# schematic-cnc.net
KiCad netlist of a schematic drawn in EAGLE
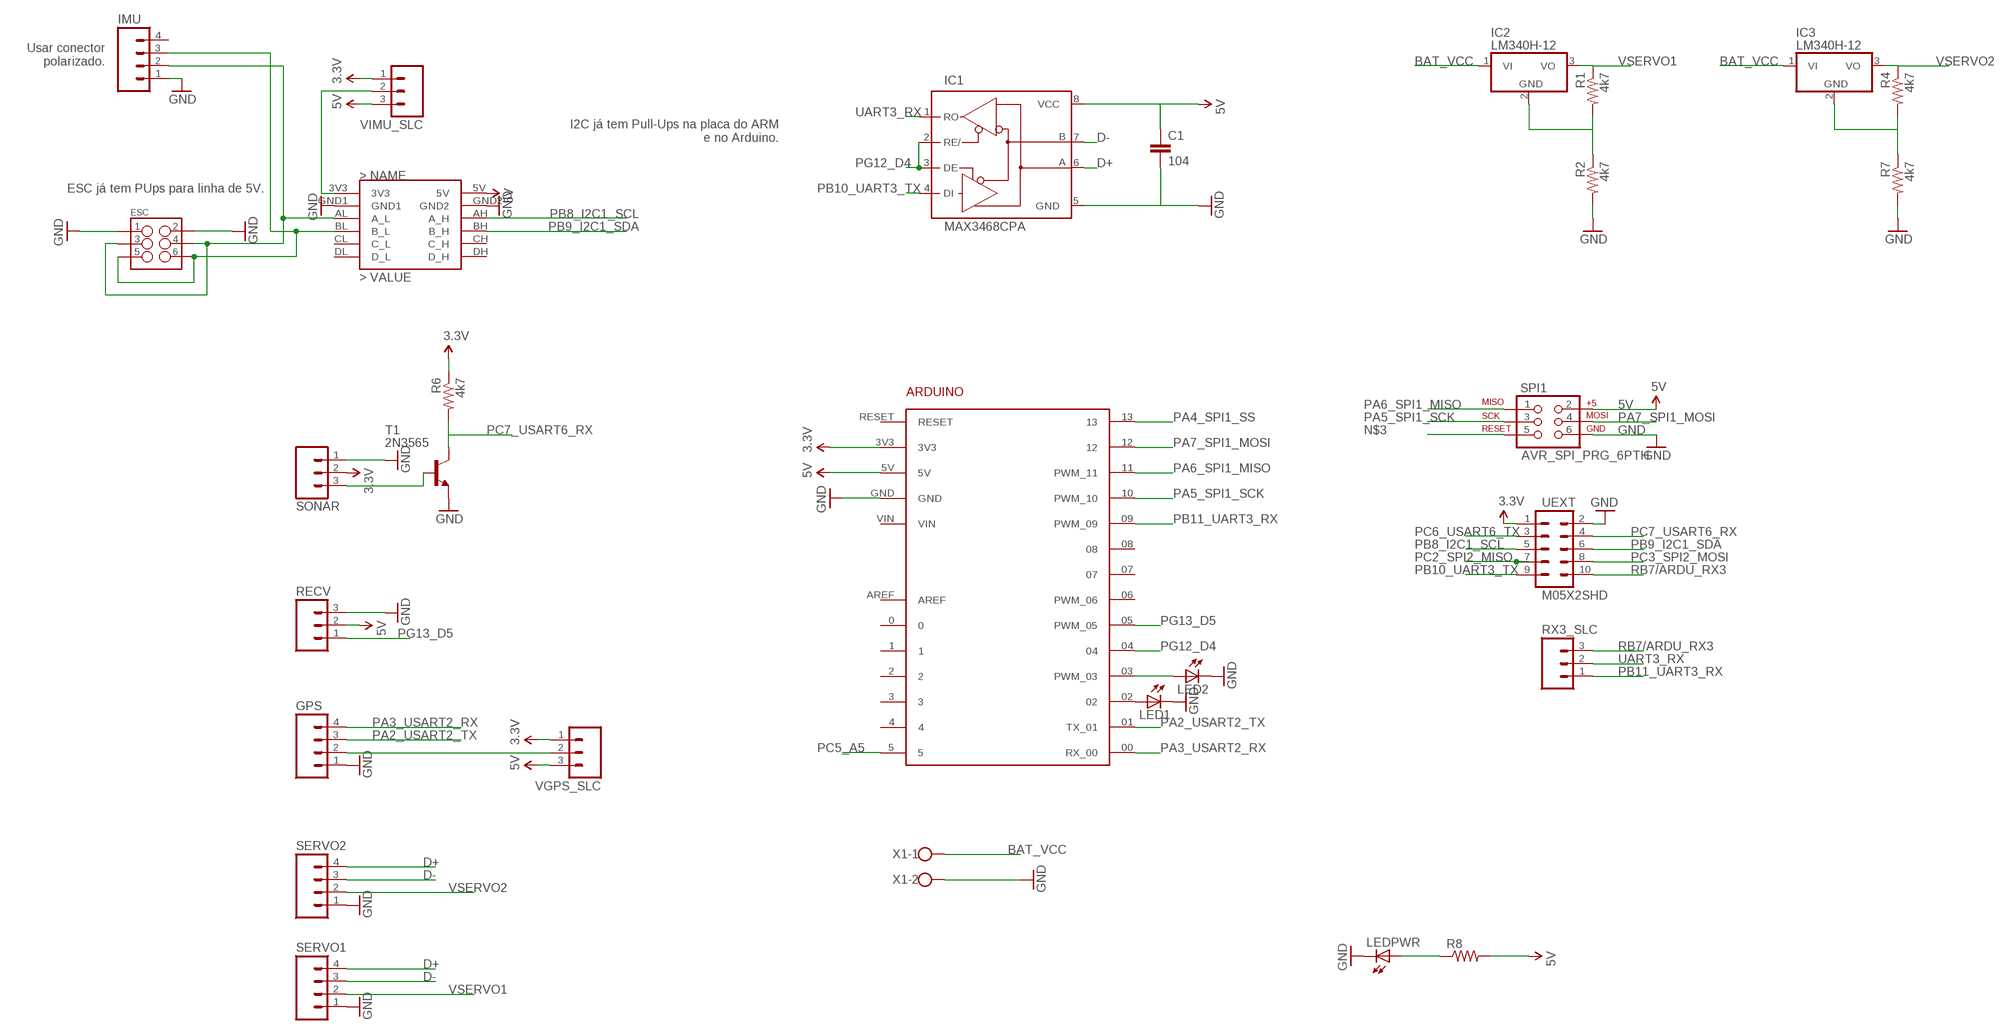
[diagram p0: schematic, sheet 1]

(export (version "E")
  (design (tool "Eeschema 10.0.6"))
  (components
    (comp (ref "ARDUINO1")
      (value "ARDUINO")
      (footprint "eagle-import:ARDUINO")
      (libsource (lib "eagle-import") (part "ARDUINO"))
    )
    (comp (ref "C1")
      (value "104")
      (footprint "eagle-import:CAP-PTH-SMALL-KIT")
      (libsource (lib "eagle-import") (part "0.1UF-50V-20%(PTH)KIT-EZ"))
    )
    (comp (ref "ESC")
      (value "M03X22X3_SILK_SM")
      (footprint "eagle-import:2X3")
      (libsource (lib "eagle-import") (part "M03X22X3_SILK_SM"))
    )
    (comp (ref "GPS")
      (value "M04PTH")
      (footprint "eagle-import:1X04")
      (libsource (lib "eagle-import") (part "M04PTH"))
    )
    (comp (ref "IC1")
      (value "MAX3468CPA")
      (footprint "eagle-import:DIL08")
      (libsource (lib "eagle-import") (part "MAX34PA68C"))
    )
    (comp (ref "IC2")
      (value "LM340H-12")
      (footprint "eagle-import:TO220H")
      (libsource (lib "eagle-import") (part "LM340?-H12"))
    )
    (comp (ref "IC3")
      (value "LM340H-12")
      (footprint "eagle-import:TO220H")
      (libsource (lib "eagle-import") (part "LM340?-H12"))
    )
    (comp (ref "IMU")
      (value "M04PTH")
      (footprint "eagle-import:1X04")
      (libsource (lib "eagle-import") (part "M04PTH"))
    )
    (comp (ref "LED1")
      (value "LED3MM")
      (footprint "eagle-import:LED3MM")
      (libsource (lib "eagle-import") (part "LED3MM"))
    )
    (comp (ref "LED2")
      (value "LED3MM")
      (footprint "eagle-import:LED3MM")
      (libsource (lib "eagle-import") (part "LED3MM"))
    )
    (comp (ref "LEDPWR")
      (value "LED3MM")
      (footprint "eagle-import:LED3MM")
      (libsource (lib "eagle-import") (part "LED3MM"))
    )
    (comp (ref "R1")
      (value "4k7")
      (footprint "eagle-import:0309V")
      (libsource (lib "eagle-import") (part "R-US_0309/V"))
    )
    (comp (ref "R2")
      (value "4k7")
      (footprint "eagle-import:0204_7")
      (libsource (lib "eagle-import") (part "R-US_0204/7"))
    )
    (comp (ref "R4")
      (value "4k7")
      (footprint "eagle-import:0309V")
      (libsource (lib "eagle-import") (part "R-US_0309/V"))
    )
    (comp (ref "R6")
      (value "4k7")
      (footprint "eagle-import:0204_7")
      (libsource (lib "eagle-import") (part "R-US_0204/7"))
    )
    (comp (ref "R7")
      (value "4k7")
      (footprint "eagle-import:0204_7")
      (libsource (lib "eagle-import") (part "R-US_0204/7"))
    )
    (comp (ref "R8")
      (value "RESISTORPTH-1/6W")
      (footprint "eagle-import:1_6W-RES")
      (libsource (lib "eagle-import") (part "RESISTORPTH-1/6W"))
    )
    (comp (ref "RECV")
      (value "M03PTH")
      (footprint "eagle-import:1X03")
      (libsource (lib "eagle-import") (part "M03PTH"))
    )
    (comp (ref "RX3_SLC")
      (value "M03PTH")
      (footprint "eagle-import:1X03")
      (libsource (lib "eagle-import") (part "M03PTH"))
    )
    (comp (ref "SERVO1")
      (value "M04PTH")
      (footprint "eagle-import:1X04")
      (libsource (lib "eagle-import") (part "M04PTH"))
    )
    (comp (ref "SERVO2")
      (value "M04PTH")
      (footprint "eagle-import:1X04")
      (libsource (lib "eagle-import") (part "M04PTH"))
    )
    (comp (ref "SONAR")
      (value "M03PTH")
      (footprint "eagle-import:1X03")
      (libsource (lib "eagle-import") (part "M03PTH"))
    )
    (comp (ref "SPI1")
      (value "AVR_SPI_PRG_6PTH")
      (footprint "eagle-import:2X3")
      (libsource (lib "eagle-import") (part "AVR_SPI_PRG_6PTH"))
    )
    (comp (ref "T1")
      (value "2N3565")
      (footprint "eagle-import:TO92")
      (libsource (lib "eagle-import") (part "2N3565"))
    )
    (comp (ref "U$1")
      (value "JYMCU_LOGIC_LEVEL_CONVERTER")
      (footprint "eagle-import:JYMCU_LOGIC_LEVEL_SHIFTER_DIP")
      (libsource (lib "eagle-import") (part "JYMCU_LOGIC_LEVEL_CONVERTER"))
    )
    (comp (ref "UEXT")
      (value "M05X2SHD")
      (footprint "eagle-import:2X5-SHROUDED")
      (libsource (lib "eagle-import") (part "M05X2SHD"))
    )
    (comp (ref "VGPS_SLC")
      (value "M03PTH")
      (footprint "eagle-import:1X03")
      (libsource (lib "eagle-import") (part "M03PTH"))
    )
    (comp (ref "VIMU_SLC")
      (value "M03PTH")
      (footprint "eagle-import:1X03")
      (libsource (lib "eagle-import") (part "M03PTH"))
    )
    (comp (ref "X1")
      (value "W237-102")
      (footprint "eagle-import:W237-102")
      (fields (field (name "MPN") "237-102"))
      (libsource (lib "eagle-import") (part "W237-102"))
    )
  )
  (nets
    (net (code "1") (name "/BAT_VCC") (class "Default")
      (node (ref "IC2") (pin "1") (pinfunction "VI_1") (pintype "input"))
      (node (ref "IC3") (pin "1") (pinfunction "VI_1") (pintype "input"))
      (node (ref "X1") (pin "1") (pinfunction "KL_1") (pintype "passive"))
    )
    (net (code "2") (name "/D+") (class "Default")
      (node (ref "IC1") (pin "6") (pinfunction "A_6") (pintype "passive"))
      (node (ref "SERVO1") (pin "4") (pinfunction "4_4") (pintype "passive"))
      (node (ref "SERVO2") (pin "4") (pinfunction "4_4") (pintype "passive"))
    )
    (net (code "3") (name "/D-") (class "Default")
      (node (ref "IC1") (pin "7") (pinfunction "B_7") (pintype "passive"))
      (node (ref "SERVO1") (pin "3") (pinfunction "3_3") (pintype "passive"))
      (node (ref "SERVO2") (pin "3") (pinfunction "3_3") (pintype "passive"))
    )
    (net (code "4") (name "/N$3") (class "Default")
      (node (ref "SPI1") (pin "5") (pinfunction "5_5") (pintype "passive"))
    )
    (net (code "5") (name "/PA2_USART2_TX") (class "Default")
      (node (ref "ARDUINO1") (pin "01") (pinfunction "TX_01_01") (pintype "bidirectional"))
      (node (ref "GPS") (pin "3") (pinfunction "3_3") (pintype "passive"))
    )
    (net (code "6") (name "/PA3_USART2_RX") (class "Default")
      (node (ref "ARDUINO1") (pin "00") (pinfunction "RX_00_00") (pintype "bidirectional"))
      (node (ref "GPS") (pin "4") (pinfunction "4_4") (pintype "passive"))
    )
    (net (code "7") (name "/PA4_SPI1_SS") (class "Default")
      (node (ref "ARDUINO1") (pin "13") (pinfunction "13_13") (pintype "bidirectional"))
    )
    (net (code "8") (name "/PA5_SPI1_SCK") (class "Default")
      (node (ref "ARDUINO1") (pin "10") (pinfunction "PWM_10_10") (pintype "bidirectional"))
      (node (ref "SPI1") (pin "3") (pinfunction "3_3") (pintype "passive"))
    )
    (net (code "9") (name "/PA6_SPI1_MISO") (class "Default")
      (node (ref "ARDUINO1") (pin "11") (pinfunction "PWM_11_11") (pintype "bidirectional"))
      (node (ref "SPI1") (pin "1") (pinfunction "1_1") (pintype "passive"))
    )
    (net (code "10") (name "/PA7_SPI1_MOSI") (class "Default")
      (node (ref "ARDUINO1") (pin "12") (pinfunction "12_12") (pintype "bidirectional"))
      (node (ref "SPI1") (pin "4") (pinfunction "4_4") (pintype "passive"))
    )
    (net (code "11") (name "/PB8_I2C1_SCL") (class "Default")
      (node (ref "U$1") (pin "AH") (pinfunction "A_H_AH") (pintype "bidirectional"))
      (node (ref "UEXT") (pin "5") (pinfunction "5_5") (pintype "passive"))
    )
    (net (code "12") (name "/PB9_I2C1_SDA") (class "Default")
      (node (ref "U$1") (pin "BH") (pinfunction "B_H_BH") (pintype "bidirectional"))
      (node (ref "UEXT") (pin "6") (pinfunction "6_6") (pintype "passive"))
    )
    (net (code "13") (name "/PB10_UART3_TX") (class "Default")
      (node (ref "IC1") (pin "4") (pinfunction "DI_4") (pintype "input"))
      (node (ref "UEXT") (pin "9") (pinfunction "9_9") (pintype "passive"))
    )
    (net (code "14") (name "/PB11_UART3_RX") (class "Default")
      (node (ref "ARDUINO1") (pin "09") (pinfunction "PWM_09_09") (pintype "bidirectional"))
      (node (ref "RX3_SLC") (pin "1") (pinfunction "1_1") (pintype "passive"))
    )
    (net (code "15") (name "/PC2_SPI2_MISO") (class "Default")
      (node (ref "UEXT") (pin "7") (pinfunction "7_7") (pintype "passive"))
    )
    (net (code "16") (name "/PC3_SPI2_MOSI") (class "Default")
      (node (ref "UEXT") (pin "8") (pinfunction "8_8") (pintype "passive"))
    )
    (net (code "17") (name "/PC5_A5") (class "Default")
      (node (ref "ARDUINO1") (pin "5") (pinfunction "5_5") (pintype "bidirectional"))
    )
    (net (code "18") (name "/PC6_USART6_TX") (class "Default")
      (node (ref "UEXT") (pin "3") (pinfunction "3_3") (pintype "passive"))
    )
    (net (code "19") (name "/PC7_USART6_RX") (class "Default")
      (node (ref "R6") (pin "2") (pinfunction "2_2") (pintype "passive"))
      (node (ref "T1") (pin "1") (pinfunction "C_1") (pintype "passive"))
      (node (ref "UEXT") (pin "4") (pinfunction "4_4") (pintype "passive"))
    )
    (net (code "20") (name "/PG12_D4") (class "Default")
      (node (ref "ARDUINO1") (pin "04") (pinfunction "04_04") (pintype "bidirectional"))
      (node (ref "IC1") (pin "2") (pinfunction "RE/_2") (pintype "input"))
      (node (ref "IC1") (pin "3") (pinfunction "DE_3") (pintype "input"))
    )
    (net (code "21") (name "/PG13_D5") (class "Default")
      (node (ref "ARDUINO1") (pin "05") (pinfunction "PWM_05_05") (pintype "bidirectional"))
      (node (ref "RECV") (pin "1") (pinfunction "1_1") (pintype "passive"))
    )
    (net (code "22") (name "/RB7{slash}ARDU_RX3") (class "Default")
      (node (ref "RX3_SLC") (pin "3") (pinfunction "3_3") (pintype "passive"))
      (node (ref "UEXT") (pin "10") (pinfunction "10_10") (pintype "passive"))
    )
    (net (code "23") (name "/UART3_RX") (class "Default")
      (node (ref "IC1") (pin "1") (pinfunction "RO_1") (pintype "output"))
      (node (ref "RX3_SLC") (pin "2") (pinfunction "2_2") (pintype "passive"))
    )
    (net (code "24") (name "/VSERVO1") (class "Default")
      (node (ref "IC2") (pin "3") (pinfunction "VO_3") (pintype "passive"))
      (node (ref "R1") (pin "1") (pinfunction "1_1") (pintype "passive"))
      (node (ref "SERVO1") (pin "2") (pinfunction "2_2") (pintype "passive"))
    )
    (net (code "25") (name "/VSERVO2") (class "Default")
      (node (ref "IC3") (pin "3") (pinfunction "VO_3") (pintype "passive"))
      (node (ref "R4") (pin "1") (pinfunction "1_1") (pintype "passive"))
      (node (ref "SERVO2") (pin "2") (pinfunction "2_2") (pintype "passive"))
    )
    (net (code "26") (name "3.3V") (class "Default")
      (node (ref "ARDUINO1") (pin "3V3") (pinfunction "3V3_3V3") (pintype "bidirectional"))
      (node (ref "R6") (pin "1") (pinfunction "1_1") (pintype "passive"))
      (node (ref "SONAR") (pin "2") (pinfunction "2_2") (pintype "passive"))
      (node (ref "UEXT") (pin "1") (pinfunction "1_1") (pintype "passive"))
      (node (ref "VGPS_SLC") (pin "1") (pinfunction "1_1") (pintype "passive"))
      (node (ref "VIMU_SLC") (pin "1") (pinfunction "1_1") (pintype "passive"))
    )
    (net (code "27") (name "5V") (class "Default")
      (node (ref "ARDUINO1") (pin "5V") (pinfunction "5V_5V") (pintype "bidirectional"))
      (node (ref "C1") (pin "1") (pinfunction "1_1") (pintype "passive"))
      (node (ref "IC1") (pin "8") (pinfunction "VCC_8") (pintype "power_in"))
      (node (ref "R8") (pin "2") (pinfunction "2_2") (pintype "passive"))
      (node (ref "RECV") (pin "2") (pinfunction "2_2") (pintype "passive"))
      (node (ref "SPI1") (pin "2") (pinfunction "2_2") (pintype "passive"))
      (node (ref "U$1") (pin "5V") (pinfunction "5V_5V") (pintype "bidirectional"))
      (node (ref "VGPS_SLC") (pin "3") (pinfunction "3_3") (pintype "passive"))
      (node (ref "VIMU_SLC") (pin "3") (pinfunction "3_3") (pintype "passive"))
    )
    (net (code "28") (name "GND") (class "Default")
      (node (ref "ARDUINO1") (pin "GND") (pinfunction "GND_GND") (pintype "bidirectional"))
      (node (ref "C1") (pin "2") (pinfunction "2_2") (pintype "passive"))
      (node (ref "ESC") (pin "1") (pinfunction "1_1") (pintype "bidirectional"))
      (node (ref "ESC") (pin "2") (pinfunction "2_2") (pintype "bidirectional"))
      (node (ref "GPS") (pin "1") (pinfunction "1_1") (pintype "passive"))
      (node (ref "IC1") (pin "5") (pinfunction "GND_5") (pintype "power_in"))
      (node (ref "IMU") (pin "1") (pinfunction "1_1") (pintype "passive"))
      (node (ref "LED1") (pin "K") (pinfunction "C_K") (pintype "passive"))
      (node (ref "LED2") (pin "K") (pinfunction "C_K") (pintype "passive"))
      (node (ref "LEDPWR") (pin "K") (pinfunction "C_K") (pintype "passive"))
      (node (ref "R2") (pin "2") (pinfunction "2_2") (pintype "passive"))
      (node (ref "R7") (pin "2") (pinfunction "2_2") (pintype "passive"))
      (node (ref "RECV") (pin "3") (pinfunction "3_3") (pintype "passive"))
      (node (ref "SERVO1") (pin "1") (pinfunction "1_1") (pintype "passive"))
      (node (ref "SERVO2") (pin "1") (pinfunction "1_1") (pintype "passive"))
      (node (ref "SONAR") (pin "1") (pinfunction "1_1") (pintype "passive"))
      (node (ref "SPI1") (pin "6") (pinfunction "6_6") (pintype "passive"))
      (node (ref "T1") (pin "3") (pinfunction "E_3") (pintype "passive"))
      (node (ref "U$1") (pin "GND1") (pinfunction "GND1_GND1") (pintype "bidirectional"))
      (node (ref "U$1") (pin "GND2") (pinfunction "GND2_GND2") (pintype "bidirectional"))
      (node (ref "UEXT") (pin "2") (pinfunction "2_2") (pintype "passive"))
      (node (ref "X1") (pin "2") (pinfunction "KL_2") (pintype "passive"))
    )
    (net (code "29") (name "Net-(ARDUINO1-PWM_03)") (class "Default")
      (node (ref "ARDUINO1") (pin "03") (pinfunction "PWM_03_03") (pintype "bidirectional"))
      (node (ref "LED2") (pin "A") (pinfunction "A_A") (pintype "passive"))
    )
    (net (code "30") (name "Net-(ARDUINO1-Pad02)") (class "Default")
      (node (ref "ARDUINO1") (pin "02") (pinfunction "02_02") (pintype "bidirectional"))
      (node (ref "LED1") (pin "A") (pinfunction "A_A") (pintype "passive"))
    )
    (net (code "31") (name "Net-(GPS-Pad2)") (class "Default")
      (node (ref "GPS") (pin "2") (pinfunction "2_2") (pintype "passive"))
      (node (ref "VGPS_SLC") (pin "2") (pinfunction "2_2") (pintype "passive"))
    )
    (net (code "32") (name "Net-(IC2-GND)") (class "Default")
      (node (ref "IC2") (pin "2") (pinfunction "GND_2") (pintype "passive"))
      (node (ref "R1") (pin "2") (pinfunction "2_2") (pintype "passive"))
      (node (ref "R2") (pin "1") (pinfunction "1_1") (pintype "passive"))
    )
    (net (code "33") (name "Net-(IC3-GND)") (class "Default")
      (node (ref "IC3") (pin "2") (pinfunction "GND_2") (pintype "passive"))
      (node (ref "R4") (pin "2") (pinfunction "2_2") (pintype "passive"))
      (node (ref "R7") (pin "1") (pinfunction "1_1") (pintype "passive"))
    )
    (net (code "34") (name "Net-(LEDPWR-PadA)") (class "Default")
      (node (ref "LEDPWR") (pin "A") (pinfunction "A_A") (pintype "passive"))
      (node (ref "R8") (pin "1") (pinfunction "1_1") (pintype "passive"))
    )
    (net (code "35") (name "Net-(T1-B)") (class "Default")
      (node (ref "SONAR") (pin "3") (pinfunction "3_3") (pintype "passive"))
      (node (ref "T1") (pin "2") (pinfunction "B_2") (pintype "passive"))
    )
    (net (code "36") (name "Net-(U$1-A_L)") (class "Default")
      (node (ref "ESC") (pin "3") (pinfunction "3_3") (pintype "bidirectional"))
      (node (ref "ESC") (pin "4") (pinfunction "4_4") (pintype "bidirectional"))
      (node (ref "IMU") (pin "2") (pinfunction "2_2") (pintype "passive"))
      (node (ref "U$1") (pin "AL") (pinfunction "A_L_AL") (pintype "bidirectional"))
    )
    (net (code "37") (name "Net-(U$1-B_L)") (class "Default")
      (node (ref "ESC") (pin "5") (pinfunction "5_5") (pintype "bidirectional"))
      (node (ref "ESC") (pin "6") (pinfunction "6_6") (pintype "bidirectional"))
      (node (ref "IMU") (pin "3") (pinfunction "3_3") (pintype "passive"))
      (node (ref "U$1") (pin "BL") (pinfunction "B_L_BL") (pintype "bidirectional"))
    )
    (net (code "38") (name "Net-(U$1-Pad3V3)") (class "Default")
      (node (ref "U$1") (pin "3V3") (pinfunction "3V3_3V3") (pintype "bidirectional"))
      (node (ref "VIMU_SLC") (pin "2") (pinfunction "2_2") (pintype "passive"))
    )
    (net (code "39") (name "unconnected-(ARDUINO1-PWM_06-Pad06)") (class "Default")
      (node (ref "ARDUINO1") (pin "06") (pinfunction "PWM_06_06") (pintype "bidirectional"))
    )
    (net (code "40") (name "unconnected-(ARDUINO1-Pad0)") (class "Default")
      (node (ref "ARDUINO1") (pin "0") (pinfunction "0_0") (pintype "bidirectional"))
    )
    (net (code "41") (name "unconnected-(ARDUINO1-Pad1)") (class "Default")
      (node (ref "ARDUINO1") (pin "1") (pinfunction "1_1") (pintype "bidirectional"))
    )
    (net (code "42") (name "unconnected-(ARDUINO1-Pad2)") (class "Default")
      (node (ref "ARDUINO1") (pin "2") (pinfunction "2_2") (pintype "bidirectional"))
    )
    (net (code "43") (name "unconnected-(ARDUINO1-Pad3)") (class "Default")
      (node (ref "ARDUINO1") (pin "3") (pinfunction "3_3") (pintype "bidirectional"))
    )
    (net (code "44") (name "unconnected-(ARDUINO1-Pad4)") (class "Default")
      (node (ref "ARDUINO1") (pin "4") (pinfunction "4_4") (pintype "bidirectional"))
    )
    (net (code "45") (name "unconnected-(ARDUINO1-Pad07)") (class "Default")
      (node (ref "ARDUINO1") (pin "07") (pinfunction "07_07") (pintype "bidirectional"))
    )
    (net (code "46") (name "unconnected-(ARDUINO1-Pad08)") (class "Default")
      (node (ref "ARDUINO1") (pin "08") (pinfunction "08_08") (pintype "bidirectional"))
    )
    (net (code "47") (name "unconnected-(ARDUINO1-PadAREF)") (class "Default")
      (node (ref "ARDUINO1") (pin "AREF") (pinfunction "AREF_AREF") (pintype "bidirectional"))
    )
    (net (code "48") (name "unconnected-(ARDUINO1-PadRESET)") (class "Default")
      (node (ref "ARDUINO1") (pin "RESET") (pinfunction "RESET_RESET") (pintype "bidirectional"))
    )
    (net (code "49") (name "unconnected-(ARDUINO1-PadVIN)") (class "Default")
      (node (ref "ARDUINO1") (pin "VIN") (pinfunction "VIN_VIN") (pintype "bidirectional"))
    )
    (net (code "50") (name "unconnected-(IMU-Pad4)") (class "Default")
      (node (ref "IMU") (pin "4") (pinfunction "4_4") (pintype "passive"))
    )
    (net (code "51") (name "unconnected-(U$1-C_H-PadCH)") (class "Default")
      (node (ref "U$1") (pin "CH") (pinfunction "C_H_CH") (pintype "bidirectional"))
    )
    (net (code "52") (name "unconnected-(U$1-C_L-PadCL)") (class "Default")
      (node (ref "U$1") (pin "CL") (pinfunction "C_L_CL") (pintype "bidirectional"))
    )
    (net (code "53") (name "unconnected-(U$1-D_H-PadDH)") (class "Default")
      (node (ref "U$1") (pin "DH") (pinfunction "D_H_DH") (pintype "bidirectional"))
    )
    (net (code "54") (name "unconnected-(U$1-D_L-PadDL)") (class "Default")
      (node (ref "U$1") (pin "DL") (pinfunction "D_L_DL") (pintype "bidirectional"))
    )
  )
)
